# Etage_Reception_2.net
KiCad netlist of a schematic drawn in Altium Designer
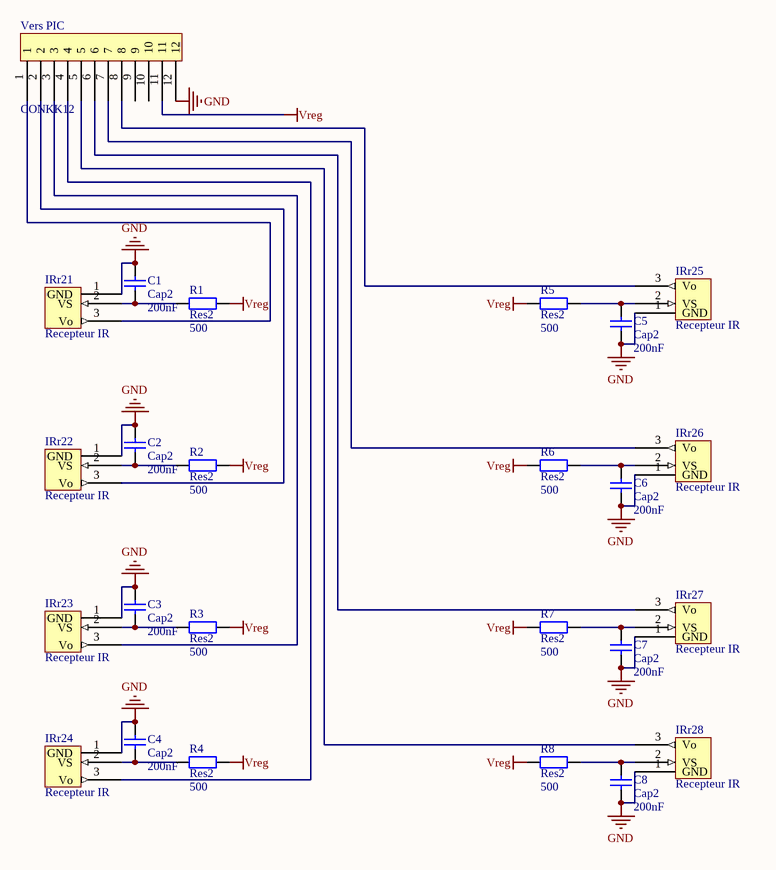
[diagram p0: Etage Reception 2.SchDoc]

(export (version "E")
  (design (tool "Eeschema 10.0.6"))
  (components
    (comp (ref "C1")
      (value "Cap2")
      (footprint "CAPA2")
      (description "Capacitor")
      (fields (field (name "ALTIUM_VALUE") "200nF") (field (name "PUBLISHER") "Altium Limited"))
      (libsource (lib "LIBRAIRIE_INTEGREE_PHELMA1") (part "Cap2"))
    )
    (comp (ref "C2")
      (value "Cap2")
      (footprint "CAPA2")
      (description "Capacitor")
      (fields (field (name "ALTIUM_VALUE") "200nF") (field (name "PUBLISHER") "Altium Limited"))
      (libsource (lib "LIBRAIRIE_INTEGREE_PHELMA1") (part "Cap2"))
    )
    (comp (ref "C3")
      (value "Cap2")
      (footprint "CAPA2")
      (description "Capacitor")
      (fields (field (name "ALTIUM_VALUE") "200nF") (field (name "PUBLISHER") "Altium Limited"))
      (libsource (lib "LIBRAIRIE_INTEGREE_PHELMA1") (part "Cap2"))
    )
    (comp (ref "C4")
      (value "Cap2")
      (footprint "CAPA2")
      (description "Capacitor")
      (fields (field (name "ALTIUM_VALUE") "200nF") (field (name "PUBLISHER") "Altium Limited"))
      (libsource (lib "LIBRAIRIE_INTEGREE_PHELMA1") (part "Cap2"))
    )
    (comp (ref "C5")
      (value "Cap2")
      (footprint "CAPA2")
      (description "Capacitor")
      (fields (field (name "ALTIUM_VALUE") "200nF") (field (name "PUBLISHER") "Altium Limited"))
      (libsource (lib "LIBRAIRIE_INTEGREE_PHELMA1") (part "Cap2"))
    )
    (comp (ref "C6")
      (value "Cap2")
      (footprint "CAPA2")
      (description "Capacitor")
      (fields (field (name "ALTIUM_VALUE") "200nF") (field (name "PUBLISHER") "Altium Limited"))
      (libsource (lib "LIBRAIRIE_INTEGREE_PHELMA1") (part "Cap2"))
    )
    (comp (ref "C7")
      (value "Cap2")
      (footprint "CAPA2")
      (description "Capacitor")
      (fields (field (name "ALTIUM_VALUE") "200nF") (field (name "PUBLISHER") "Altium Limited"))
      (libsource (lib "LIBRAIRIE_INTEGREE_PHELMA1") (part "Cap2"))
    )
    (comp (ref "C8")
      (value "Cap2")
      (footprint "CAPA2")
      (description "Capacitor")
      (fields (field (name "ALTIUM_VALUE") "200nF") (field (name "PUBLISHER") "Altium Limited"))
      (libsource (lib "LIBRAIRIE_INTEGREE_PHELMA1") (part "Cap2"))
    )
    (comp (ref "IRr21")
      (value "Recepteur IR")
      (footprint "TSOP1138")
      (libsource (lib "") (part "TSOP1138_1"))
    )
    (comp (ref "IRr22")
      (value "Recepteur IR")
      (footprint "TSOP1138")
      (libsource (lib "") (part "TSOP1138_1"))
    )
    (comp (ref "IRr23")
      (value "Recepteur IR")
      (footprint "TSOP1138")
      (libsource (lib "") (part "TSOP1138_1"))
    )
    (comp (ref "IRr24")
      (value "Recepteur IR")
      (footprint "TSOP1138")
      (libsource (lib "") (part "TSOP1138_1"))
    )
    (comp (ref "IRr25")
      (value "Recepteur IR")
      (footprint "TSOP1138")
      (libsource (lib "TSOP1138") (part "TSOP1138"))
    )
    (comp (ref "IRr26")
      (value "Recepteur IR")
      (footprint "TSOP1138")
      (libsource (lib "TSOP1138") (part "TSOP1138"))
    )
    (comp (ref "IRr27")
      (value "Recepteur IR")
      (footprint "TSOP1138")
      (libsource (lib "TSOP1138") (part "TSOP1138"))
    )
    (comp (ref "IRr28")
      (value "Recepteur IR")
      (footprint "TSOP1138")
      (libsource (lib "TSOP1138") (part "TSOP1138"))
    )
    (comp (ref "R1")
      (value "Res2")
      (footprint "res5_1/4W")
      (description "Resistor")
      (fields (field (name "ALTIUM_VALUE") "500") (field (name "PUBLISHER") "Altium Limited"))
      (libsource (lib "LIBRAIRIE_INTEGREE_PHELMA1") (part "Res2"))
    )
    (comp (ref "R2")
      (value "Res2")
      (footprint "res5_1/4W")
      (description "Resistor")
      (fields (field (name "ALTIUM_VALUE") "500") (field (name "PUBLISHER") "Altium Limited"))
      (libsource (lib "LIBRAIRIE_INTEGREE_PHELMA1") (part "Res2"))
    )
    (comp (ref "R3")
      (value "Res2")
      (footprint "res5_1/4W")
      (description "Resistor")
      (fields (field (name "ALTIUM_VALUE") "500") (field (name "PUBLISHER") "Altium Limited"))
      (libsource (lib "LIBRAIRIE_INTEGREE_PHELMA1") (part "Res2"))
    )
    (comp (ref "R4")
      (value "Res2")
      (footprint "res5_1/4W")
      (description "Resistor")
      (fields (field (name "ALTIUM_VALUE") "500") (field (name "PUBLISHER") "Altium Limited"))
      (libsource (lib "LIBRAIRIE_INTEGREE_PHELMA1") (part "Res2"))
    )
    (comp (ref "R5")
      (value "Res2")
      (footprint "res5_1/4W")
      (description "Resistor")
      (fields (field (name "ALTIUM_VALUE") "500") (field (name "PUBLISHER") "Altium Limited"))
      (libsource (lib "") (part "Res2_1"))
    )
    (comp (ref "R6")
      (value "Res2")
      (footprint "res5_1/4W")
      (description "Resistor")
      (fields (field (name "ALTIUM_VALUE") "500") (field (name "PUBLISHER") "Altium Limited"))
      (libsource (lib "") (part "Res2_1"))
    )
    (comp (ref "R7")
      (value "Res2")
      (footprint "res5_1/4W")
      (description "Resistor")
      (fields (field (name "ALTIUM_VALUE") "500") (field (name "PUBLISHER") "Altium Limited"))
      (libsource (lib "") (part "Res2_1"))
    )
    (comp (ref "R8")
      (value "Res2")
      (footprint "res5_1/4W")
      (description "Resistor")
      (fields (field (name "ALTIUM_VALUE") "500") (field (name "PUBLISHER") "Altium Limited"))
      (libsource (lib "") (part "Res2_1"))
    )
    (comp (ref "Vers PIC")
      (value "CONKK12")
      (footprint "CONKK12")
      (libsource (lib "INTEGRATED_LIBRARY1_CONNECTEURS") (part "CONKK12"))
    )
  )
  (nets
    (net (code "1") (name "GND") (class "Default")
      (node (ref "C1") (pin "2") (pinfunction "2_2") (pintype "passive"))
      (node (ref "C2") (pin "2") (pinfunction "2_2") (pintype "passive"))
      (node (ref "C3") (pin "2") (pinfunction "2_2") (pintype "passive"))
      (node (ref "C4") (pin "2") (pinfunction "2_2") (pintype "passive"))
      (node (ref "C5") (pin "2") (pinfunction "2_2") (pintype "passive"))
      (node (ref "C6") (pin "2") (pinfunction "2_2") (pintype "passive"))
      (node (ref "C7") (pin "2") (pinfunction "2_2") (pintype "passive"))
      (node (ref "C8") (pin "2") (pinfunction "2_2") (pintype "passive"))
      (node (ref "IRr21") (pin "1") (pinfunction "GND_1") (pintype "passive"))
      (node (ref "IRr22") (pin "1") (pinfunction "GND_1") (pintype "passive"))
      (node (ref "IRr23") (pin "1") (pinfunction "GND_1") (pintype "passive"))
      (node (ref "IRr24") (pin "1") (pinfunction "GND_1") (pintype "passive"))
      (node (ref "IRr25") (pin "1") (pinfunction "GND_1") (pintype "passive"))
      (node (ref "IRr26") (pin "1") (pinfunction "GND_1") (pintype "passive"))
      (node (ref "IRr27") (pin "1") (pinfunction "GND_1") (pintype "passive"))
      (node (ref "IRr28") (pin "1") (pinfunction "GND_1") (pintype "passive"))
      (node (ref "Vers PIC") (pin "12") (pinfunction "12_12") (pintype "passive"))
    )
    (net (code "2") (name "Net-(IRr21-VS)") (class "Default")
      (node (ref "C1") (pin "1") (pinfunction "1_1") (pintype "passive"))
      (node (ref "IRr21") (pin "2") (pinfunction "VS_2") (pintype "input"))
      (node (ref "R1") (pin "1") (pinfunction "1_1") (pintype "passive"))
    )
    (net (code "3") (name "Net-(IRr21-Vo)") (class "Default")
      (node (ref "IRr21") (pin "3") (pinfunction "Vo_3") (pintype "output"))
      (node (ref "Vers PIC") (pin "1") (pinfunction "1_1") (pintype "passive"))
    )
    (net (code "4") (name "Net-(IRr22-VS)") (class "Default")
      (node (ref "C2") (pin "1") (pinfunction "1_1") (pintype "passive"))
      (node (ref "IRr22") (pin "2") (pinfunction "VS_2") (pintype "input"))
      (node (ref "R2") (pin "1") (pinfunction "1_1") (pintype "passive"))
    )
    (net (code "5") (name "Net-(IRr22-Vo)") (class "Default")
      (node (ref "IRr22") (pin "3") (pinfunction "Vo_3") (pintype "output"))
      (node (ref "Vers PIC") (pin "2") (pinfunction "2_2") (pintype "passive"))
    )
    (net (code "6") (name "Net-(IRr23-VS)") (class "Default")
      (node (ref "C3") (pin "1") (pinfunction "1_1") (pintype "passive"))
      (node (ref "IRr23") (pin "2") (pinfunction "VS_2") (pintype "input"))
      (node (ref "R3") (pin "1") (pinfunction "1_1") (pintype "passive"))
    )
    (net (code "7") (name "Net-(IRr23-Vo)") (class "Default")
      (node (ref "IRr23") (pin "3") (pinfunction "Vo_3") (pintype "output"))
      (node (ref "Vers PIC") (pin "3") (pinfunction "3_3") (pintype "passive"))
    )
    (net (code "8") (name "Net-(IRr24-VS)") (class "Default")
      (node (ref "C4") (pin "1") (pinfunction "1_1") (pintype "passive"))
      (node (ref "IRr24") (pin "2") (pinfunction "VS_2") (pintype "input"))
      (node (ref "R4") (pin "1") (pinfunction "1_1") (pintype "passive"))
    )
    (net (code "9") (name "Net-(IRr24-Vo)") (class "Default")
      (node (ref "IRr24") (pin "3") (pinfunction "Vo_3") (pintype "output"))
      (node (ref "Vers PIC") (pin "4") (pinfunction "4_4") (pintype "passive"))
    )
    (net (code "10") (name "Net-(IRr25-VS)") (class "Default")
      (node (ref "C5") (pin "1") (pinfunction "1_1") (pintype "passive"))
      (node (ref "IRr25") (pin "2") (pinfunction "VS_2") (pintype "input"))
      (node (ref "R5") (pin "1") (pinfunction "1_1") (pintype "passive"))
    )
    (net (code "11") (name "Net-(IRr25-Vo)") (class "Default")
      (node (ref "IRr25") (pin "3") (pinfunction "Vo_3") (pintype "output"))
      (node (ref "Vers PIC") (pin "8") (pinfunction "8_8") (pintype "passive"))
    )
    (net (code "12") (name "Net-(IRr26-VS)") (class "Default")
      (node (ref "C6") (pin "1") (pinfunction "1_1") (pintype "passive"))
      (node (ref "IRr26") (pin "2") (pinfunction "VS_2") (pintype "input"))
      (node (ref "R6") (pin "1") (pinfunction "1_1") (pintype "passive"))
    )
    (net (code "13") (name "Net-(IRr26-Vo)") (class "Default")
      (node (ref "IRr26") (pin "3") (pinfunction "Vo_3") (pintype "output"))
      (node (ref "Vers PIC") (pin "7") (pinfunction "7_7") (pintype "passive"))
    )
    (net (code "14") (name "Net-(IRr27-VS)") (class "Default")
      (node (ref "C7") (pin "1") (pinfunction "1_1") (pintype "passive"))
      (node (ref "IRr27") (pin "2") (pinfunction "VS_2") (pintype "input"))
      (node (ref "R7") (pin "1") (pinfunction "1_1") (pintype "passive"))
    )
    (net (code "15") (name "Net-(IRr27-Vo)") (class "Default")
      (node (ref "IRr27") (pin "3") (pinfunction "Vo_3") (pintype "output"))
      (node (ref "Vers PIC") (pin "6") (pinfunction "6_6") (pintype "passive"))
    )
    (net (code "16") (name "Net-(IRr28-VS)") (class "Default")
      (node (ref "C8") (pin "1") (pinfunction "1_1") (pintype "passive"))
      (node (ref "IRr28") (pin "2") (pinfunction "VS_2") (pintype "input"))
      (node (ref "R8") (pin "1") (pinfunction "1_1") (pintype "passive"))
    )
    (net (code "17") (name "Net-(IRr28-Vo)") (class "Default")
      (node (ref "IRr28") (pin "3") (pinfunction "Vo_3") (pintype "output"))
      (node (ref "Vers PIC") (pin "5") (pinfunction "5_5") (pintype "passive"))
    )
    (net (code "18") (name "Vreg") (class "Default")
      (node (ref "R1") (pin "2") (pinfunction "2_2") (pintype "passive"))
      (node (ref "R2") (pin "2") (pinfunction "2_2") (pintype "passive"))
      (node (ref "R3") (pin "2") (pinfunction "2_2") (pintype "passive"))
      (node (ref "R4") (pin "2") (pinfunction "2_2") (pintype "passive"))
      (node (ref "R5") (pin "2") (pinfunction "2_2") (pintype "passive"))
      (node (ref "R6") (pin "2") (pinfunction "2_2") (pintype "passive"))
      (node (ref "R7") (pin "2") (pinfunction "2_2") (pintype "passive"))
      (node (ref "R8") (pin "2") (pinfunction "2_2") (pintype "passive"))
      (node (ref "Vers PIC") (pin "11") (pinfunction "11_11") (pintype "passive"))
    )
    (net (code "19") (name "unconnected-(Vers PIC-Pad9)") (class "Default")
      (node (ref "Vers PIC") (pin "9") (pinfunction "9_9") (pintype "passive"))
    )
    (net (code "20") (name "unconnected-(Vers PIC-Pad10)") (class "Default")
      (node (ref "Vers PIC") (pin "10") (pinfunction "10_10") (pintype "passive"))
    )
  )
)
